# merope-relays.net
KiCad netlist of a schematic drawn in EAGLE
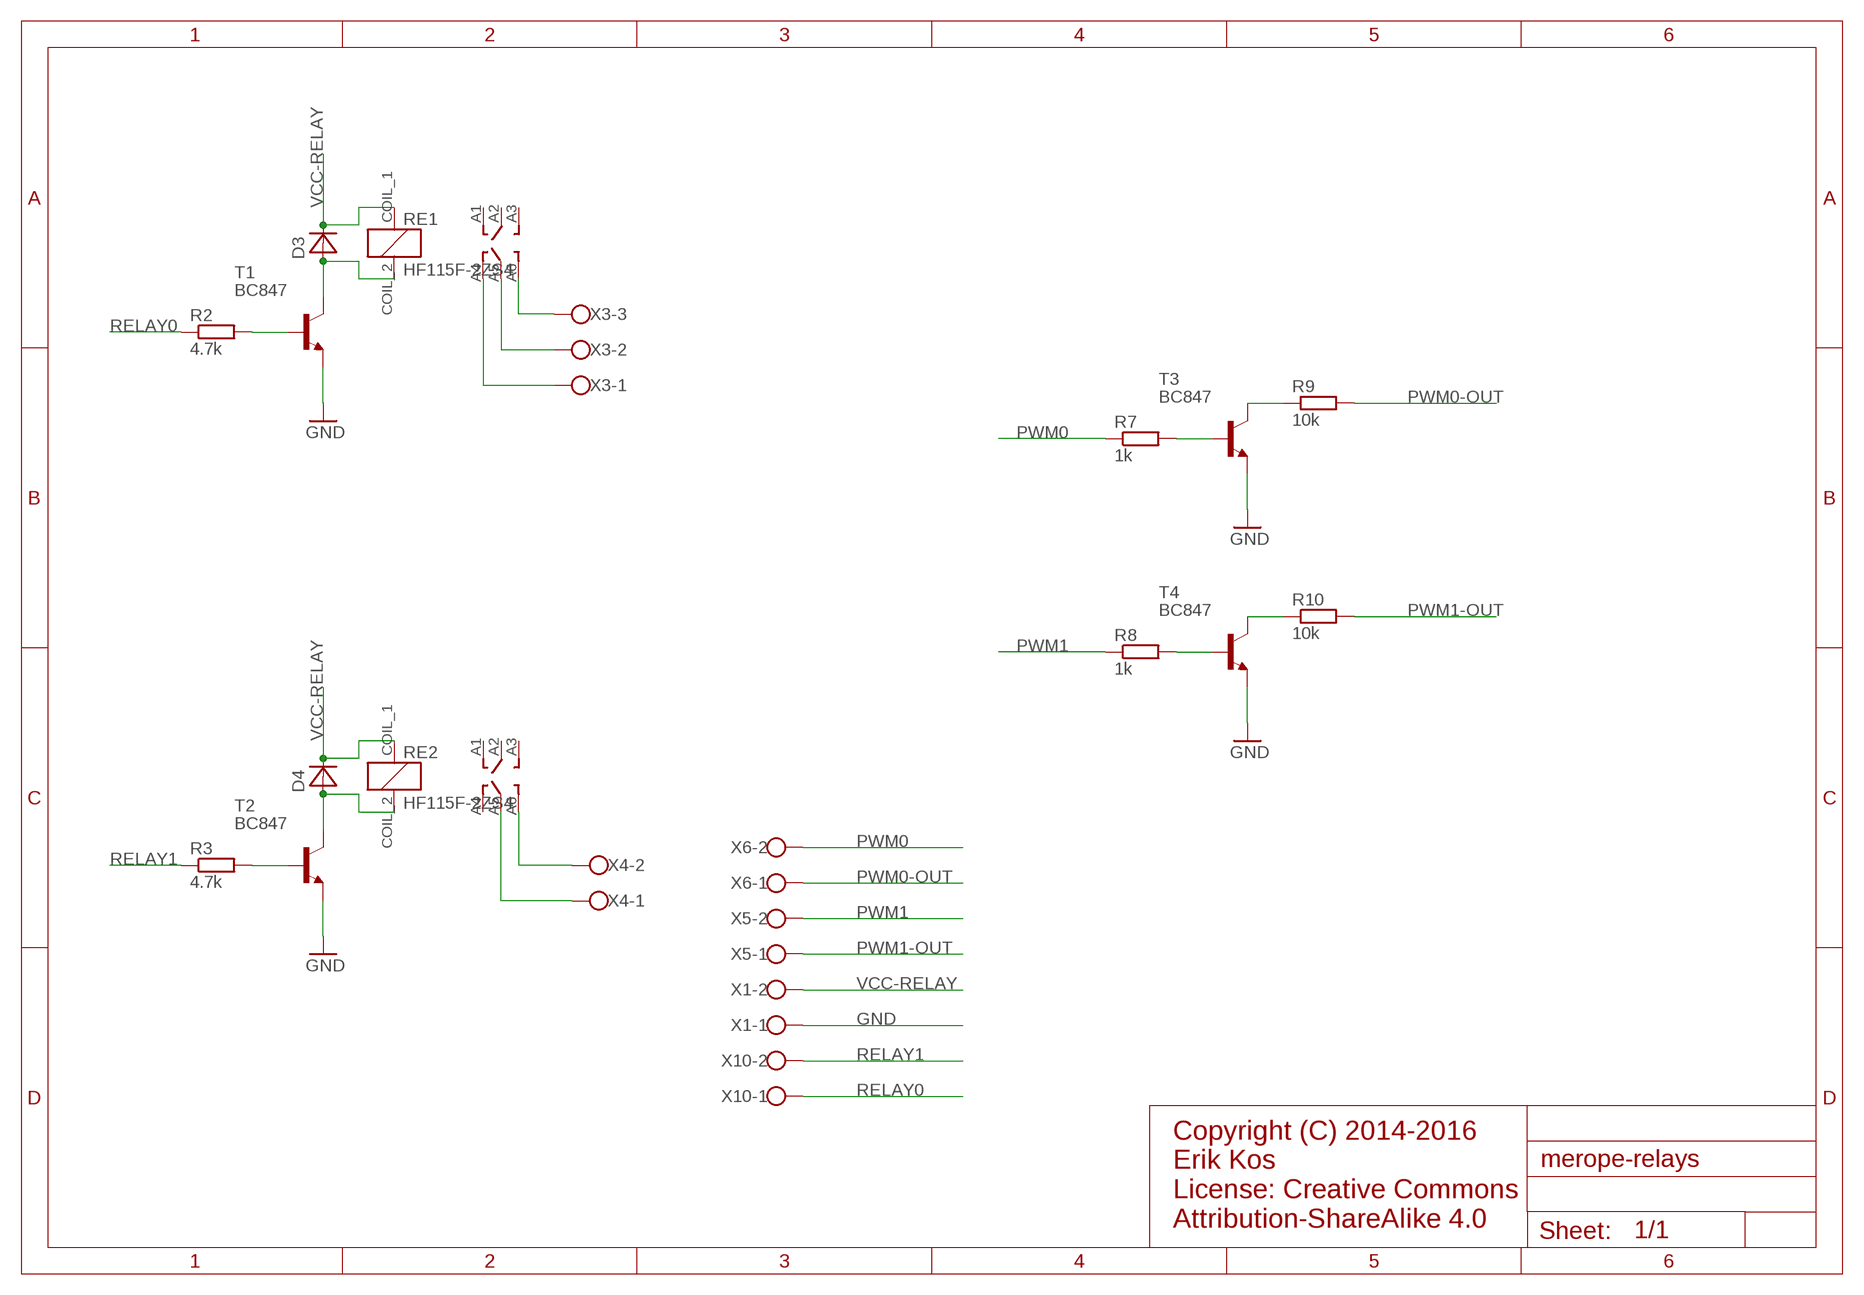
[diagram p0: schematic, sheet 1]

(export (version "E")
  (design (tool "Eeschema 10.0.6"))
  (components
    (comp (ref "D3")
      (value "DIODE_0805")
      (footprint "eagle-import:R0805")
      (libsource (lib "eagle-import") (part "DIODE_0805"))
    )
    (comp (ref "D4")
      (value "DIODE_0805")
      (footprint "eagle-import:R0805")
      (libsource (lib "eagle-import") (part "DIODE_0805"))
    )
    (comp (ref "R2")
      (value "4.7k")
      (footprint "eagle-import:M0805")
      (libsource (lib "eagle-import") (part "R-EU_M0805"))
    )
    (comp (ref "R3")
      (value "4.7k")
      (footprint "eagle-import:M0805")
      (libsource (lib "eagle-import") (part "R-EU_M0805"))
    )
    (comp (ref "R7")
      (value "1k")
      (footprint "eagle-import:M0805")
      (libsource (lib "eagle-import") (part "R-EU_M0805"))
    )
    (comp (ref "R8")
      (value "1k")
      (footprint "eagle-import:M0805")
      (libsource (lib "eagle-import") (part "R-EU_M0805"))
    )
    (comp (ref "R9")
      (value "10k")
      (footprint "eagle-import:M0805")
      (libsource (lib "eagle-import") (part "R-EU_M0805"))
    )
    (comp (ref "R10")
      (value "10k")
      (footprint "eagle-import:M0805")
      (libsource (lib "eagle-import") (part "R-EU_M0805"))
    )
    (comp (ref "RE1")
      (value "HF115F-2ZS4")
      (footprint "eagle-import:HF115F")
      (libsource (lib "eagle-import") (part "HF115F-2ZS4"))
    )
    (comp (ref "RE2")
      (value "HF115F-2ZS4")
      (footprint "eagle-import:HF115F")
      (libsource (lib "eagle-import") (part "HF115F-2ZS4"))
    )
    (comp (ref "T1")
      (value "BC847")
      (footprint "eagle-import:SOT23-BEC")
      (libsource (lib "eagle-import") (part "-NPN-SOT23-BECBC817-25"))
    )
    (comp (ref "T2")
      (value "BC847")
      (footprint "eagle-import:SOT23-BEC")
      (libsource (lib "eagle-import") (part "-NPN-SOT23-BECBC817-25"))
    )
    (comp (ref "T3")
      (value "BC847")
      (footprint "eagle-import:SOT23-BEC")
      (libsource (lib "eagle-import") (part "-NPN-SOT23-BECBC817-25"))
    )
    (comp (ref "T4")
      (value "BC847")
      (footprint "eagle-import:SOT23-BEC")
      (libsource (lib "eagle-import") (part "-NPN-SOT23-BECBC817-25"))
    )
    (comp (ref "X1")
      (value "TERMINAL_BLOCK_35_2")
      (footprint "eagle-import:TERMINAL_BLOCK_35_2")
      (libsource (lib "eagle-import") (part "TERMINAL_BLOCK_35_2"))
    )
    (comp (ref "X3")
      (value "TERMINAL_BLOCK_5_3")
      (footprint "eagle-import:TERMINAL_BLOCK_5_3")
      (libsource (lib "eagle-import") (part "TERMINAL_BLOCK_5_3"))
    )
    (comp (ref "X4")
      (value "TERMINAL_BLOCK_5_2")
      (footprint "eagle-import:TERMINAL_BLOCK_5_2")
      (libsource (lib "eagle-import") (part "TERMINAL_BLOCK_5_2"))
    )
    (comp (ref "X5")
      (value "TERMINAL_BLOCK_35_2")
      (footprint "eagle-import:TERMINAL_BLOCK_35_2")
      (libsource (lib "eagle-import") (part "TERMINAL_BLOCK_35_2"))
    )
    (comp (ref "X6")
      (value "TERMINAL_BLOCK_35_2")
      (footprint "eagle-import:TERMINAL_BLOCK_35_2")
      (libsource (lib "eagle-import") (part "TERMINAL_BLOCK_35_2"))
    )
    (comp (ref "X10")
      (value "TERMINAL_BLOCK_35_2")
      (footprint "eagle-import:TERMINAL_BLOCK_35_2")
      (libsource (lib "eagle-import") (part "TERMINAL_BLOCK_35_2"))
    )
  )
  (nets
    (net (code "1") (name "/PWM0") (class "Default")
      (node (ref "R7") (pin "1") (pinfunction "1_1") (pintype "passive"))
      (node (ref "X6") (pin "2") (pinfunction "KL_2") (pintype "passive"))
    )
    (net (code "2") (name "/PWM0-OUT") (class "Default")
      (node (ref "R9") (pin "2") (pinfunction "2_2") (pintype "passive"))
      (node (ref "X6") (pin "1") (pinfunction "KL_1") (pintype "passive"))
    )
    (net (code "3") (name "/PWM1") (class "Default")
      (node (ref "R8") (pin "1") (pinfunction "1_1") (pintype "passive"))
      (node (ref "X5") (pin "2") (pinfunction "KL_2") (pintype "passive"))
    )
    (net (code "4") (name "/PWM1-OUT") (class "Default")
      (node (ref "R10") (pin "2") (pinfunction "2_2") (pintype "passive"))
      (node (ref "X5") (pin "1") (pinfunction "KL_1") (pintype "passive"))
    )
    (net (code "5") (name "/RELAY0") (class "Default")
      (node (ref "R2") (pin "1") (pinfunction "1_1") (pintype "passive"))
      (node (ref "X10") (pin "1") (pinfunction "KL_1") (pintype "passive"))
    )
    (net (code "6") (name "/RELAY1") (class "Default")
      (node (ref "R3") (pin "1") (pinfunction "1_1") (pintype "passive"))
      (node (ref "X10") (pin "2") (pinfunction "KL_2") (pintype "passive"))
    )
    (net (code "7") (name "/VCC-RELAY") (class "Default")
      (node (ref "D3") (pin "2") (pinfunction "C_2") (pintype "passive"))
      (node (ref "D4") (pin "2") (pinfunction "C_2") (pintype "passive"))
      (node (ref "RE1") (pin "COIL_1") (pinfunction "COIL_1_COIL_1") (pintype "passive"))
      (node (ref "RE2") (pin "COIL_1") (pinfunction "COIL_1_COIL_1") (pintype "passive"))
      (node (ref "X1") (pin "2") (pinfunction "KL_2") (pintype "passive"))
    )
    (net (code "8") (name "GND") (class "Default")
      (node (ref "T1") (pin "E") (pinfunction "E_E") (pintype "passive"))
      (node (ref "T2") (pin "E") (pinfunction "E_E") (pintype "passive"))
      (node (ref "T3") (pin "E") (pinfunction "E_E") (pintype "passive"))
      (node (ref "T4") (pin "E") (pinfunction "E_E") (pintype "passive"))
      (node (ref "X1") (pin "1") (pinfunction "KL_1") (pintype "passive"))
    )
    (net (code "9") (name "Net-(D3-A)") (class "Default")
      (node (ref "D3") (pin "1") (pinfunction "A_1") (pintype "passive"))
      (node (ref "RE1") (pin "COIL_2") (pinfunction "COIL_2_COIL_2") (pintype "passive"))
      (node (ref "T1") (pin "C") (pinfunction "C_C") (pintype "passive"))
    )
    (net (code "10") (name "Net-(D4-A)") (class "Default")
      (node (ref "D4") (pin "1") (pinfunction "A_1") (pintype "passive"))
      (node (ref "RE2") (pin "COIL_2") (pinfunction "COIL_2_COIL_2") (pintype "passive"))
      (node (ref "T2") (pin "C") (pinfunction "C_C") (pintype "passive"))
    )
    (net (code "11") (name "Net-(R2-Pad2)") (class "Default")
      (node (ref "R2") (pin "2") (pinfunction "2_2") (pintype "passive"))
      (node (ref "T1") (pin "B") (pinfunction "B_B") (pintype "passive"))
    )
    (net (code "12") (name "Net-(R3-Pad2)") (class "Default")
      (node (ref "R3") (pin "2") (pinfunction "2_2") (pintype "passive"))
      (node (ref "T2") (pin "B") (pinfunction "B_B") (pintype "passive"))
    )
    (net (code "13") (name "Net-(R7-Pad2)") (class "Default")
      (node (ref "R7") (pin "2") (pinfunction "2_2") (pintype "passive"))
      (node (ref "T3") (pin "B") (pinfunction "B_B") (pintype "passive"))
    )
    (net (code "14") (name "Net-(R8-Pad2)") (class "Default")
      (node (ref "R8") (pin "2") (pinfunction "2_2") (pintype "passive"))
      (node (ref "T4") (pin "B") (pinfunction "B_B") (pintype "passive"))
    )
    (net (code "15") (name "Net-(R9-Pad1)") (class "Default")
      (node (ref "R9") (pin "1") (pinfunction "1_1") (pintype "passive"))
      (node (ref "T3") (pin "C") (pinfunction "C_C") (pintype "passive"))
    )
    (net (code "16") (name "Net-(R10-Pad1)") (class "Default")
      (node (ref "R10") (pin "1") (pinfunction "1_1") (pintype "passive"))
      (node (ref "T4") (pin "C") (pinfunction "C_C") (pintype "passive"))
    )
    (net (code "17") (name "Net-(X3A-KL)") (class "Default")
      (node (ref "RE1") (pin "A4") (pinfunction "A4_A4") (pintype "passive"))
      (node (ref "X3") (pin "1") (pinfunction "KL_1") (pintype "passive"))
    )
    (net (code "18") (name "Net-(X3B-KL)") (class "Default")
      (node (ref "RE1") (pin "A5") (pinfunction "A5_A5") (pintype "passive"))
      (node (ref "X3") (pin "2") (pinfunction "KL_2") (pintype "passive"))
    )
    (net (code "19") (name "Net-(X3C-KL)") (class "Default")
      (node (ref "RE1") (pin "A6") (pinfunction "A6_A6") (pintype "passive"))
      (node (ref "X3") (pin "3") (pinfunction "KL_3") (pintype "passive"))
    )
    (net (code "20") (name "Net-(X4A-KL)") (class "Default")
      (node (ref "RE2") (pin "A5") (pinfunction "A5_A5") (pintype "passive"))
      (node (ref "X4") (pin "1") (pinfunction "KL_1") (pintype "passive"))
    )
    (net (code "21") (name "Net-(X4B-KL)") (class "Default")
      (node (ref "RE2") (pin "A6") (pinfunction "A6_A6") (pintype "passive"))
      (node (ref "X4") (pin "2") (pinfunction "KL_2") (pintype "passive"))
    )
    (net (code "22") (name "unconnected-(RE1-PadA1)") (class "Default")
      (node (ref "RE1") (pin "A1") (pinfunction "A1_A1") (pintype "passive"))
    )
    (net (code "23") (name "unconnected-(RE1-PadA2)") (class "Default")
      (node (ref "RE1") (pin "A2") (pinfunction "A2_A2") (pintype "passive"))
    )
    (net (code "24") (name "unconnected-(RE1-PadA3)") (class "Default")
      (node (ref "RE1") (pin "A3") (pinfunction "A3_A3") (pintype "passive"))
    )
    (net (code "25") (name "unconnected-(RE2-PadA1)") (class "Default")
      (node (ref "RE2") (pin "A1") (pinfunction "A1_A1") (pintype "passive"))
    )
    (net (code "26") (name "unconnected-(RE2-PadA2)") (class "Default")
      (node (ref "RE2") (pin "A2") (pinfunction "A2_A2") (pintype "passive"))
    )
    (net (code "27") (name "unconnected-(RE2-PadA3)") (class "Default")
      (node (ref "RE2") (pin "A3") (pinfunction "A3_A3") (pintype "passive"))
    )
    (net (code "28") (name "unconnected-(RE2-PadA4)") (class "Default")
      (node (ref "RE2") (pin "A4") (pinfunction "A4_A4") (pintype "passive"))
    )
  )
)
